# 1-Schematic_Purple_Eye.net
KiCad netlist of a schematic drawn in EasyEDA
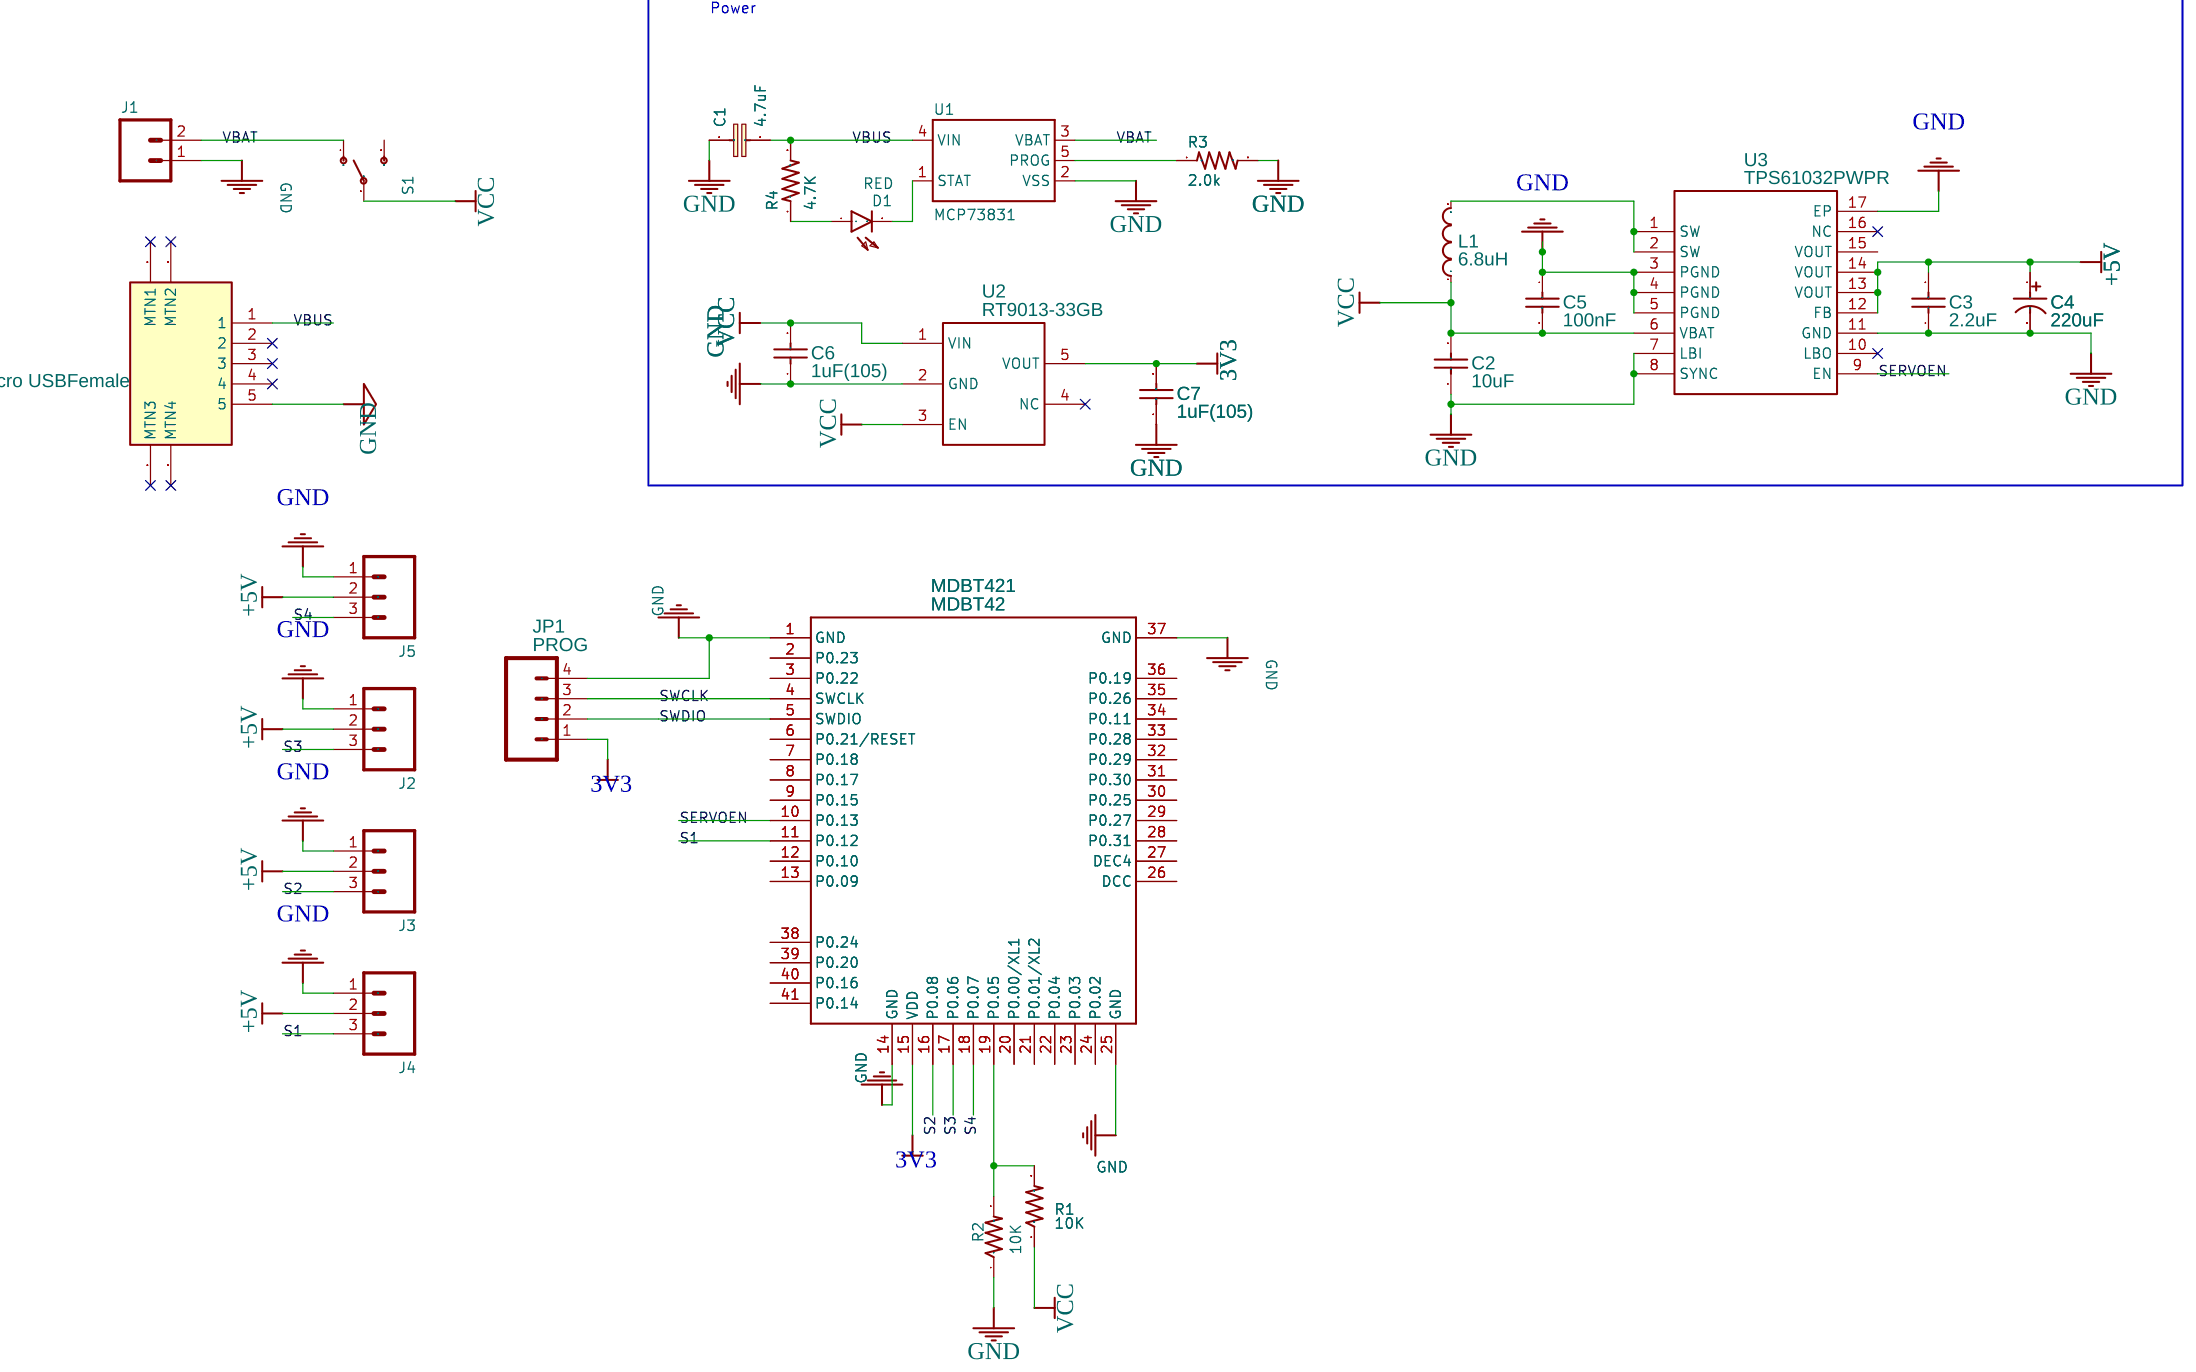
[diagram p0: schematic sheet]

(export (version "E")
  (design (tool "Eeschema 10.0.6"))
  (components
    (comp (ref "C1") (value "4.7uF") (libsource (lib "") (part "Unknown_350_-510")))
    (comp (ref "C2")
      (value "10uF")
      (fields
        (field (name "BOM_Manufacturer Part") "CL10A475MQ8NNNC")
        (field (name "BOM_Supplier Part") "C154959")
      )
      (libsource (lib "") (part "CL10A475MQ8NNNC"))
    )
    (comp (ref "C3")
      (value "2.2uF")
      (fields
        (field (name "BOM_Manufacturer Part") "CL10A225KP8NNNC")
        (field (name "BOM_Supplier Part") "C1607")
      )
      (libsource (lib "") (part "CL10A225KP8NNNC"))
    )
    (comp (ref "C4")
      (value "220uF")
      (fields
        (field (name "BOM_Manufacturer Part") "T491C227K006AT")
        (field (name "BOM_Supplier Part") "C117035")
      )
      (libsource (lib "") (part "T491C227K006AT"))
    )
    (comp (ref "C5")
      (value "100nF")
      (fields
        (field (name "BOM_Manufacturer Part") "C0603C104K5RACTU")
        (field (name "BOM_Supplier Part") "C127833")
      )
      (libsource (lib "") (part "C0603C104K5RACTU"))
    )
    (comp (ref "C6")
      (value "1uF(105)")
      (fields
        (field (name "BOM_Manufacturer Part") "0603B105K160")
        (field (name "BOM_Supplier Part") "C108463")
      )
      (libsource (lib "") (part "0603B105K160"))
    )
    (comp (ref "C7")
      (value "1uF(105)")
      (fields
        (field (name "BOM_Manufacturer Part") "0603B105K160")
        (field (name "BOM_Supplier Part") "C108463")
      )
      (libsource (lib "") (part "0603B105K160"))
    )
    (comp (ref "D1") (value "RED") (libsource (lib "") (part "Unknown_400_-470")))
    (comp (ref "J1") (value "M02JST-PTH-2") (libsource (lib "") (part "Unknown_50_-500")))
    (comp (ref "J2") (value "M03LOCK") (libsource (lib "") (part "Unknown_175_-220")))
    (comp (ref "J3") (value "M03LOCK") (libsource (lib "") (part "Unknown_175_-150")))
    (comp (ref "J4") (value "M03LOCK") (libsource (lib "") (part "Unknown_175_-80")))
    (comp (ref "J5") (value "M03LOCK") (libsource (lib "") (part "Unknown_175_-285")))
    (comp (ref "J7")
      (value "micro USBFemale")
      (fields (field (name "BOM_Supplier Part") "C10418"))
      (libsource (lib "") (part "Unknown_80_-400"))
    )
    (comp (ref "JP1")
      (value "PROG")
      (fields (field (name "BOM_Manufacturer Part") "?"))
      (libsource (lib "") (part "Unknown_250_-230"))
    )
    (comp (ref "L1")
      (value "6.8uH")
      (fields
        (field (name "BOM_Manufacturer Part") "CDRH103RNP-6R8NC-B")
        (field (name "BOM_Supplier Part") "C167253")
      )
      (libsource (lib "") (part "CDRH103RNP-6R8NC-B"))
    )
    (comp (ref "MDBT421")
      (value "MDBT42")
      (fields (field (name "BOM_Manufacturer Part") "?"))
      (libsource (lib "") (part "Unknown_380_-265"))
    )
    (comp (ref "R1") (value "10K") (libsource (lib "") (part "Unknown_490_15")))
    (comp (ref "R2") (value "10K") (libsource (lib "") (part "Unknown_470_30")))
    (comp (ref "R3") (value "2.0k") (libsource (lib "") (part "Unknown_580_-500")))
    (comp (ref "R4") (value "4.7K") (libsource (lib "") (part "Unknown_370_-490")))
    (comp (ref "S1") (value "SWITCH-SPDTPTH_LOCK") (libsource (lib "") (part "Unknown_160_-490")))
    (comp (ref "U1") (value "MCP73831") (libsource (lib "") (part "Unknown_470_-500")))
    (comp (ref "U2")
      (value "RT9013-33GB")
      (fields (field (name "BOM_Supplier Part") "C47773"))
      (libsource (lib "") (part "Unknown_470_-390"))
    )
    (comp (ref "U3")
      (value "TPS61032PWPR")
      (fields (field (name "BOM_Supplier Part") "C88716"))
      (libsource (lib "") (part "Unknown_845_-435"))
    )
  )
  (nets
    (net (code "1") (name "+5V") (class "Default")
      (node (ref "C3") (pin "2") (pinfunction "2_2") (pintype "input"))
      (node (ref "C4") (pin "1") (pinfunction "1_1") (pintype "input"))
      (node (ref "J2") (pin "2") (pinfunction "2_2") (pintype "bidirectional"))
      (node (ref "J3") (pin "2") (pinfunction "2_2") (pintype "bidirectional"))
      (node (ref "J4") (pin "2") (pinfunction "2_2") (pintype "bidirectional"))
      (node (ref "J5") (pin "2") (pinfunction "2_2") (pintype "bidirectional"))
      (node (ref "U3") (pin "12") (pinfunction "FB_12") (pintype "unspecified"))
      (node (ref "U3") (pin "13") (pinfunction "VOUT_13") (pintype "unspecified"))
      (node (ref "U3") (pin "14") (pinfunction "VOUT_14") (pintype "unspecified"))
    )
    (net (code "2") (name "/S1") (class "Default")
      (node (ref "J4") (pin "3") (pinfunction "3_3") (pintype "bidirectional"))
      (node (ref "MDBT421") (pin "11") (pinfunction "P0.12_11") (pintype "bidirectional"))
    )
    (net (code "3") (name "/S2") (class "Default")
      (node (ref "J3") (pin "3") (pinfunction "3_3") (pintype "bidirectional"))
      (node (ref "MDBT421") (pin "16") (pinfunction "P0.08_16") (pintype "bidirectional"))
    )
    (net (code "4") (name "/S3") (class "Default")
      (node (ref "J2") (pin "3") (pinfunction "3_3") (pintype "bidirectional"))
      (node (ref "MDBT421") (pin "17") (pinfunction "P0.06_17") (pintype "bidirectional"))
    )
    (net (code "5") (name "/S4") (class "Default")
      (node (ref "J5") (pin "3") (pinfunction "3_3") (pintype "bidirectional"))
      (node (ref "MDBT421") (pin "18") (pinfunction "P0.07_18") (pintype "bidirectional"))
    )
    (net (code "6") (name "/SERVOEN") (class "Default")
      (node (ref "MDBT421") (pin "10") (pinfunction "P0.13_10") (pintype "bidirectional"))
      (node (ref "U3") (pin "9") (pinfunction "EN_9") (pintype "unspecified"))
    )
    (net (code "7") (name "/SWCLK") (class "Default")
      (node (ref "JP1") (pin "3") (pinfunction "3_3") (pintype "unspecified"))
      (node (ref "MDBT421") (pin "4") (pinfunction "SWCLK_4") (pintype "bidirectional"))
    )
    (net (code "8") (name "/SWDIO") (class "Default")
      (node (ref "JP1") (pin "2") (pinfunction "2_2") (pintype "unspecified"))
      (node (ref "MDBT421") (pin "5") (pinfunction "SWDIO_5") (pintype "bidirectional"))
    )
    (net (code "9") (name "/VBAT") (class "Default")
      (node (ref "J1") (pin "2") (pinfunction "2_2") (pintype "bidirectional"))
      (node (ref "S1") (pin "1") (pinfunction "O_1") (pintype "bidirectional"))
      (node (ref "U1") (pin "3") (pinfunction "VBAT_3") (pintype "bidirectional"))
    )
    (net (code "10") (name "/VBUS") (class "Default")
      (node (ref "C1") (pin "2") (pinfunction "2_2") (pintype "bidirectional"))
      (node (ref "J7") (pin "1") (pinfunction "1_1") (pintype "unspecified"))
      (node (ref "R4") (pin "2") (pinfunction "2_2") (pintype "bidirectional"))
      (node (ref "U1") (pin "4") (pinfunction "VIN_4") (pintype "bidirectional"))
    )
    (net (code "11") (name "3V3") (class "Default")
      (node (ref "C7") (pin "2") (pinfunction "2_2") (pintype "input"))
      (node (ref "JP1") (pin "1") (pinfunction "1_1") (pintype "unspecified"))
      (node (ref "MDBT421") (pin "15") (pinfunction "VDD_15") (pintype "bidirectional"))
      (node (ref "U2") (pin "5") (pinfunction "VOUT_5") (pintype "unspecified"))
    )
    (net (code "12") (name "GND") (class "Default")
      (node (ref "C1") (pin "1") (pinfunction "1_1") (pintype "bidirectional"))
      (node (ref "C2") (pin "1") (pinfunction "1_1") (pintype "input"))
      (node (ref "C3") (pin "1") (pinfunction "1_1") (pintype "input"))
      (node (ref "C4") (pin "2") (pinfunction "2_2") (pintype "input"))
      (node (ref "C5") (pin "1") (pinfunction "1_1") (pintype "input"))
      (node (ref "C6") (pin "1") (pinfunction "1_1") (pintype "input"))
      (node (ref "C7") (pin "1") (pinfunction "1_1") (pintype "input"))
      (node (ref "J1") (pin "1") (pinfunction "1_1") (pintype "bidirectional"))
      (node (ref "J2") (pin "1") (pinfunction "1_1") (pintype "bidirectional"))
      (node (ref "J3") (pin "1") (pinfunction "1_1") (pintype "bidirectional"))
      (node (ref "J4") (pin "1") (pinfunction "1_1") (pintype "bidirectional"))
      (node (ref "J5") (pin "1") (pinfunction "1_1") (pintype "bidirectional"))
      (node (ref "J7") (pin "5") (pinfunction "5_5") (pintype "unspecified"))
      (node (ref "JP1") (pin "4") (pinfunction "4_4") (pintype "unspecified"))
      (node (ref "MDBT421") (pin "1") (pinfunction "GND_1") (pintype "bidirectional"))
      (node (ref "MDBT421") (pin "14") (pinfunction "GND_14") (pintype "bidirectional"))
      (node (ref "MDBT421") (pin "25") (pinfunction "GND_25") (pintype "bidirectional"))
      (node (ref "MDBT421") (pin "37") (pinfunction "GND_37") (pintype "bidirectional"))
      (node (ref "R2") (pin "1") (pinfunction "1_1") (pintype "bidirectional"))
      (node (ref "R3") (pin "2") (pinfunction "2_2") (pintype "bidirectional"))
      (node (ref "U1") (pin "2") (pinfunction "VSS_2") (pintype "bidirectional"))
      (node (ref "U2") (pin "2") (pinfunction "GND_2") (pintype "unspecified"))
      (node (ref "U3") (pin "11") (pinfunction "GND_11") (pintype "unspecified"))
      (node (ref "U3") (pin "17") (pinfunction "EP_17") (pintype "unspecified"))
      (node (ref "U3") (pin "3") (pinfunction "PGND_3") (pintype "unspecified"))
      (node (ref "U3") (pin "4") (pinfunction "PGND_4") (pintype "unspecified"))
      (node (ref "U3") (pin "5") (pinfunction "PGND_5") (pintype "unspecified"))
      (node (ref "U3") (pin "7") (pinfunction "LBI_7") (pintype "unspecified"))
      (node (ref "U3") (pin "8") (pinfunction "SYNC_8") (pintype "unspecified"))
    )
    (net (code "13") (name "Net-(D1-A)") (class "Default")
      (node (ref "D1") (pin "1") (pinfunction "A_1") (pintype "bidirectional"))
      (node (ref "R4") (pin "1") (pinfunction "1_1") (pintype "bidirectional"))
    )
    (net (code "14") (name "Net-(D1-C)") (class "Default")
      (node (ref "D1") (pin "2") (pinfunction "C_2") (pintype "bidirectional"))
      (node (ref "U1") (pin "1") (pinfunction "STAT_1") (pintype "bidirectional"))
    )
    (net (code "15") (name "Net-(L1-Pad2)") (class "Default")
      (node (ref "L1") (pin "2") (pinfunction "2_2") (pintype "unspecified"))
      (node (ref "U3") (pin "1") (pinfunction "SW_1") (pintype "unspecified"))
      (node (ref "U3") (pin "2") (pinfunction "SW_2") (pintype "unspecified"))
    )
    (net (code "16") (name "Net-(MDBT421-P0.05)") (class "Default")
      (node (ref "MDBT421") (pin "19") (pinfunction "P0.05_19") (pintype "bidirectional"))
      (node (ref "R1") (pin "2") (pinfunction "2_2") (pintype "bidirectional"))
      (node (ref "R2") (pin "2") (pinfunction "2_2") (pintype "bidirectional"))
    )
    (net (code "17") (name "Net-(U1-PROG)") (class "Default")
      (node (ref "R3") (pin "1") (pinfunction "1_1") (pintype "bidirectional"))
      (node (ref "U1") (pin "5") (pinfunction "PROG_5") (pintype "bidirectional"))
    )
    (net (code "18") (name "VCC") (class "Default")
      (node (ref "C2") (pin "2") (pinfunction "2_2") (pintype "input"))
      (node (ref "C5") (pin "2") (pinfunction "2_2") (pintype "input"))
      (node (ref "C6") (pin "2") (pinfunction "2_2") (pintype "input"))
      (node (ref "L1") (pin "1") (pinfunction "1_1") (pintype "unspecified"))
      (node (ref "R1") (pin "1") (pinfunction "1_1") (pintype "bidirectional"))
      (node (ref "S1") (pin "2") (pinfunction "P_2") (pintype "bidirectional"))
      (node (ref "U2") (pin "1") (pinfunction "VIN_1") (pintype "unspecified"))
      (node (ref "U2") (pin "3") (pinfunction "EN_3") (pintype "unspecified"))
      (node (ref "U3") (pin "6") (pinfunction "VBAT_6") (pintype "unspecified"))
    )
    (net (code "19") (name "unconnected-(J7-MTN1-Pad0)") (class "Default")
      (node (ref "J7") (pin "0") (pinfunction "MTN1_0") (pintype "input+no_connect"))
    )
    (net (code "20") (name "unconnected-(J7-MTN2-Pad0)") (class "Default")
      (node (ref "J7") (pin "0") (pinfunction "MTN2_0") (pintype "input+no_connect"))
    )
    (net (code "21") (name "unconnected-(J7-MTN3-Pad0)") (class "Default")
      (node (ref "J7") (pin "0") (pinfunction "MTN3_0") (pintype "input+no_connect"))
    )
    (net (code "22") (name "unconnected-(J7-MTN4-Pad0)") (class "Default")
      (node (ref "J7") (pin "0") (pinfunction "MTN4_0") (pintype "input+no_connect"))
    )
    (net (code "23") (name "unconnected-(J7-Pad2)") (class "Default")
      (node (ref "J7") (pin "2") (pinfunction "2_2") (pintype "unspecified+no_connect"))
    )
    (net (code "24") (name "unconnected-(J7-Pad3)") (class "Default")
      (node (ref "J7") (pin "3") (pinfunction "3_3") (pintype "unspecified+no_connect"))
    )
    (net (code "25") (name "unconnected-(J7-Pad4)") (class "Default")
      (node (ref "J7") (pin "4") (pinfunction "4_4") (pintype "unspecified+no_connect"))
    )
    (net (code "26") (name "unconnected-(MDBT421-DCC-Pad26)") (class "Default")
      (node (ref "MDBT421") (pin "26") (pinfunction "DCC_26") (pintype "bidirectional"))
    )
    (net (code "27") (name "unconnected-(MDBT421-DEC4-Pad27)") (class "Default")
      (node (ref "MDBT421") (pin "27") (pinfunction "DEC4_27") (pintype "bidirectional"))
    )
    (net (code "28") (name "unconnected-(MDBT421-P0.00{slash}XL1-Pad20)") (class "Default")
      (node (ref "MDBT421") (pin "20") (pinfunction "P0.00/XL1_20") (pintype "bidirectional"))
    )
    (net (code "29") (name "unconnected-(MDBT421-P0.01{slash}XL2-Pad21)") (class "Default")
      (node (ref "MDBT421") (pin "21") (pinfunction "P0.01/XL2_21") (pintype "bidirectional"))
    )
    (net (code "30") (name "unconnected-(MDBT421-P0.02-Pad24)") (class "Default")
      (node (ref "MDBT421") (pin "24") (pinfunction "P0.02_24") (pintype "bidirectional"))
    )
    (net (code "31") (name "unconnected-(MDBT421-P0.03-Pad23)") (class "Default")
      (node (ref "MDBT421") (pin "23") (pinfunction "P0.03_23") (pintype "bidirectional"))
    )
    (net (code "32") (name "unconnected-(MDBT421-P0.04-Pad22)") (class "Default")
      (node (ref "MDBT421") (pin "22") (pinfunction "P0.04_22") (pintype "bidirectional"))
    )
    (net (code "33") (name "unconnected-(MDBT421-P0.09-Pad13)") (class "Default")
      (node (ref "MDBT421") (pin "13") (pinfunction "P0.09_13") (pintype "bidirectional"))
    )
    (net (code "34") (name "unconnected-(MDBT421-P0.10-Pad12)") (class "Default")
      (node (ref "MDBT421") (pin "12") (pinfunction "P0.10_12") (pintype "bidirectional"))
    )
    (net (code "35") (name "unconnected-(MDBT421-P0.11-Pad34)") (class "Default")
      (node (ref "MDBT421") (pin "34") (pinfunction "P0.11_34") (pintype "bidirectional"))
    )
    (net (code "36") (name "unconnected-(MDBT421-P0.14-Pad41)") (class "Default")
      (node (ref "MDBT421") (pin "41") (pinfunction "P0.14_41") (pintype "bidirectional"))
    )
    (net (code "37") (name "unconnected-(MDBT421-P0.15-Pad9)") (class "Default")
      (node (ref "MDBT421") (pin "9") (pinfunction "P0.15_9") (pintype "bidirectional"))
    )
    (net (code "38") (name "unconnected-(MDBT421-P0.16-Pad40)") (class "Default")
      (node (ref "MDBT421") (pin "40") (pinfunction "P0.16_40") (pintype "bidirectional"))
    )
    (net (code "39") (name "unconnected-(MDBT421-P0.17-Pad8)") (class "Default")
      (node (ref "MDBT421") (pin "8") (pinfunction "P0.17_8") (pintype "bidirectional"))
    )
    (net (code "40") (name "unconnected-(MDBT421-P0.18-Pad7)") (class "Default")
      (node (ref "MDBT421") (pin "7") (pinfunction "P0.18_7") (pintype "bidirectional"))
    )
    (net (code "41") (name "unconnected-(MDBT421-P0.19-Pad36)") (class "Default")
      (node (ref "MDBT421") (pin "36") (pinfunction "P0.19_36") (pintype "bidirectional"))
    )
    (net (code "42") (name "unconnected-(MDBT421-P0.20-Pad39)") (class "Default")
      (node (ref "MDBT421") (pin "39") (pinfunction "P0.20_39") (pintype "bidirectional"))
    )
    (net (code "43") (name "unconnected-(MDBT421-P0.21{slash}RESET-Pad6)") (class "Default")
      (node (ref "MDBT421") (pin "6") (pinfunction "P0.21/RESET_6") (pintype "bidirectional"))
    )
    (net (code "44") (name "unconnected-(MDBT421-P0.22-Pad3)") (class "Default")
      (node (ref "MDBT421") (pin "3") (pinfunction "P0.22_3") (pintype "bidirectional"))
    )
    (net (code "45") (name "unconnected-(MDBT421-P0.23-Pad2)") (class "Default")
      (node (ref "MDBT421") (pin "2") (pinfunction "P0.23_2") (pintype "bidirectional"))
    )
    (net (code "46") (name "unconnected-(MDBT421-P0.24-Pad38)") (class "Default")
      (node (ref "MDBT421") (pin "38") (pinfunction "P0.24_38") (pintype "bidirectional"))
    )
    (net (code "47") (name "unconnected-(MDBT421-P0.25-Pad30)") (class "Default")
      (node (ref "MDBT421") (pin "30") (pinfunction "P0.25_30") (pintype "bidirectional"))
    )
    (net (code "48") (name "unconnected-(MDBT421-P0.26-Pad35)") (class "Default")
      (node (ref "MDBT421") (pin "35") (pinfunction "P0.26_35") (pintype "bidirectional"))
    )
    (net (code "49") (name "unconnected-(MDBT421-P0.27-Pad29)") (class "Default")
      (node (ref "MDBT421") (pin "29") (pinfunction "P0.27_29") (pintype "bidirectional"))
    )
    (net (code "50") (name "unconnected-(MDBT421-P0.28-Pad33)") (class "Default")
      (node (ref "MDBT421") (pin "33") (pinfunction "P0.28_33") (pintype "bidirectional"))
    )
    (net (code "51") (name "unconnected-(MDBT421-P0.29-Pad32)") (class "Default")
      (node (ref "MDBT421") (pin "32") (pinfunction "P0.29_32") (pintype "bidirectional"))
    )
    (net (code "52") (name "unconnected-(MDBT421-P0.30-Pad31)") (class "Default")
      (node (ref "MDBT421") (pin "31") (pinfunction "P0.30_31") (pintype "bidirectional"))
    )
    (net (code "53") (name "unconnected-(MDBT421-P0.31-Pad28)") (class "Default")
      (node (ref "MDBT421") (pin "28") (pinfunction "P0.31_28") (pintype "bidirectional"))
    )
    (net (code "54") (name "unconnected-(S1-S-Pad3)") (class "Default")
      (node (ref "S1") (pin "3") (pinfunction "S_3") (pintype "bidirectional"))
    )
    (net (code "55") (name "unconnected-(U2-NC-Pad4)") (class "Default")
      (node (ref "U2") (pin "4") (pinfunction "NC_4") (pintype "unspecified+no_connect"))
    )
    (net (code "56") (name "unconnected-(U3-LBO-Pad10)") (class "Default")
      (node (ref "U3") (pin "10") (pinfunction "LBO_10") (pintype "unspecified+no_connect"))
    )
    (net (code "57") (name "unconnected-(U3-NC-Pad16)") (class "Default")
      (node (ref "U3") (pin "16") (pinfunction "NC_16") (pintype "unspecified+no_connect"))
    )
    (net (code "58") (name "unconnected-(U3-VOUT-Pad15)") (class "Default")
      (node (ref "U3") (pin "15") (pinfunction "VOUT_15") (pintype "unspecified"))
    )
  )
)
